# Gamepad_Sensors.net
KiCad netlist of a schematic drawn in Altium Designer
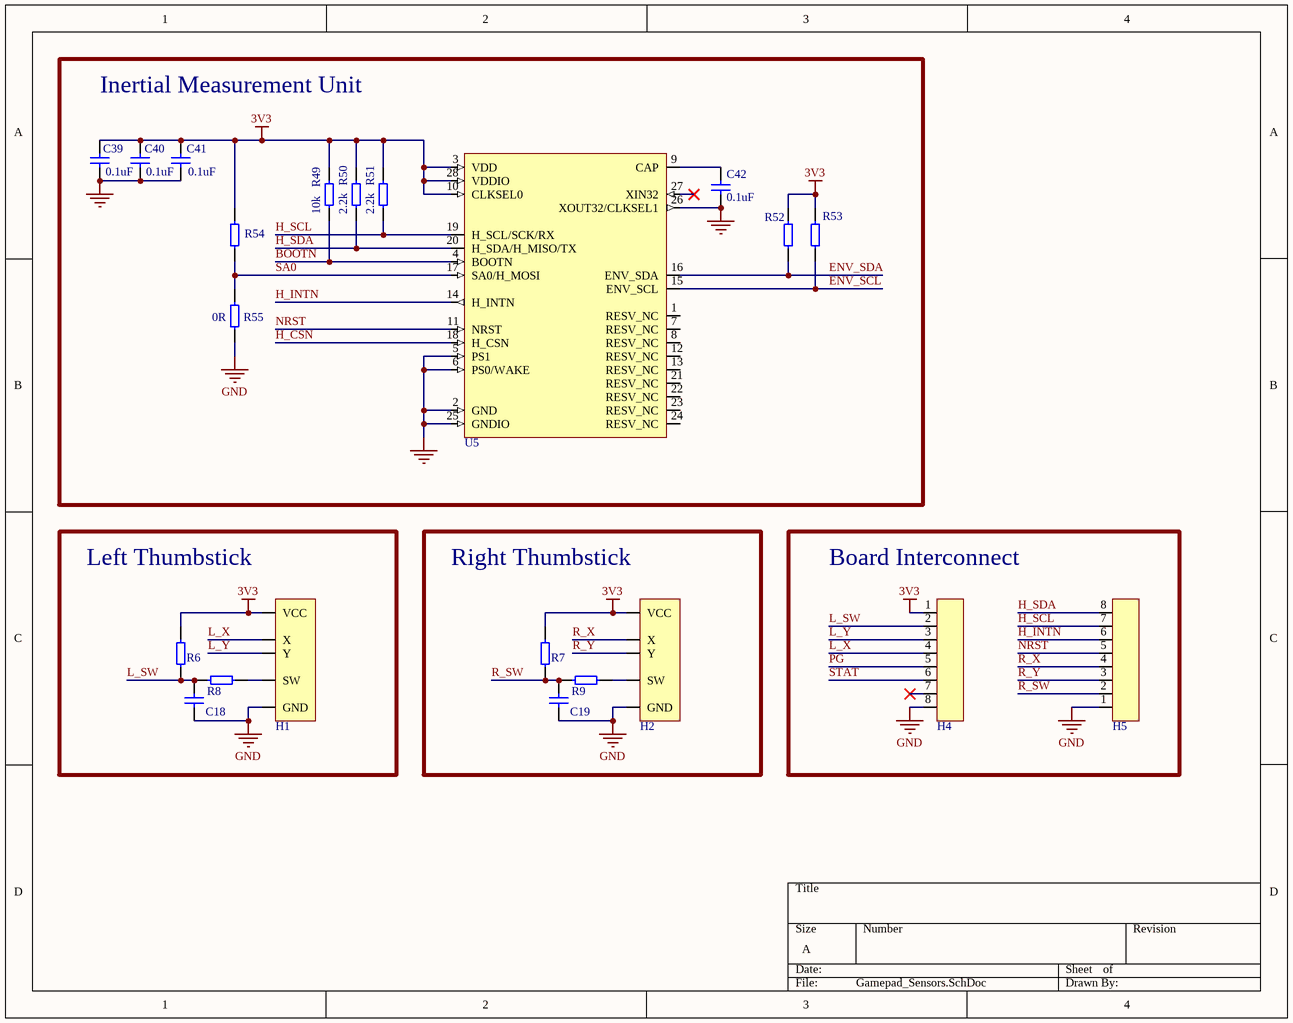
[diagram p0: Gamepad_Sensors.SchDoc]

(export (version "E")
  (design (tool "Eeschema 10.0.6"))
  (components
    (comp (ref "C18")
      (value "Capacitor")
      (footprint "0603 Capacitor")
      (libsource (lib "MoldsvorLibrary") (part "Capacitor"))
    )
    (comp (ref "C19")
      (value "Capacitor")
      (footprint "0603 Capacitor")
      (libsource (lib "MoldsvorLibrary") (part "Capacitor"))
    )
    (comp (ref "C39")
      (value "0.1uF")
      (footprint "0603 Capacitor")
      (libsource (lib "MoldsvorPassives") (part "Capacitor"))
    )
    (comp (ref "C40")
      (value "0.1uF")
      (footprint "0603 Capacitor")
      (libsource (lib "MoldsvorPassives") (part "Capacitor"))
    )
    (comp (ref "C41")
      (value "0.1uF")
      (footprint "0603 Capacitor")
      (libsource (lib "MoldsvorPassives") (part "Capacitor"))
    )
    (comp (ref "C42")
      (value "0.1uF")
      (footprint "0603 Capacitor")
      (libsource (lib "MoldsvorPassives") (part "Capacitor"))
    )
    (comp (ref "H1")
      (value "Left Thumbstick")
      (footprint "Thumbstick 2")
      (libsource (lib "Gamepad_Schematic_Library") (part "Thumbstick"))
    )
    (comp (ref "H2")
      (value "Right Thumbstick")
      (footprint "Thumbstick 2")
      (libsource (lib "Gamepad_Schematic_Library") (part "Thumbstick"))
    )
    (comp (ref "H4")
      (value "8x1 Header")
      (footprint "SMD Header Female")
      (libsource (lib "Gamepad_Schematic_Library") (part "8x1 Header"))
    )
    (comp (ref "H5")
      (value "8x1 Header")
      (footprint "SMD Header Female")
      (libsource (lib "") (part "8x1 Header_1"))
    )
    (comp (ref "R6")
      (value "Resistor")
      (footprint "0603 Resistor")
      (libsource (lib "MoldsvorLibrary") (part "Resistor"))
    )
    (comp (ref "R7")
      (value "Resistor")
      (footprint "0603 Resistor")
      (libsource (lib "MoldsvorLibrary") (part "Resistor"))
    )
    (comp (ref "R8")
      (value "Resistor")
      (footprint "0603 Resistor")
      (libsource (lib "MoldsvorLibrary") (part "Resistor"))
    )
    (comp (ref "R9")
      (value "Resistor")
      (footprint "0603 Resistor")
      (libsource (lib "MoldsvorLibrary") (part "Resistor"))
    )
    (comp (ref "R49")
      (value "10k")
      (footprint "0603 Resistor")
      (libsource (lib "MoldsvorLibrary") (part "Resistor"))
    )
    (comp (ref "R50")
      (value "2.2k")
      (footprint "0603 Resistor")
      (libsource (lib "MoldsvorPassives") (part "Resistor"))
    )
    (comp (ref "R51")
      (value "2.2k")
      (footprint "0603 Resistor")
      (libsource (lib "MoldsvorPassives") (part "Resistor"))
    )
    (comp (ref "R52")
      (value "Resistor")
      (footprint "0603 Resistor")
      (libsource (lib "MoldsvorPassives") (part "Resistor"))
    )
    (comp (ref "R53")
      (value "Resistor")
      (footprint "0603 Resistor")
      (libsource (lib "MoldsvorPassives") (part "Resistor"))
    )
    (comp (ref "R54")
      (value "Resistor")
      (footprint "0603 Resistor")
      (libsource (lib "MoldsvorLibrary") (part "Resistor"))
    )
    (comp (ref "R55")
      (value "0R")
      (footprint "0603 Resistor")
      (libsource (lib "MoldsvorLibrary") (part "Resistor"))
    )
    (comp (ref "U5")
      (value "BNO080")
      (footprint "BNO080")
      (description "IMU ACCEL/GYRO/MAG I2C 32BIT")
      (libsource (lib "Gamepad_Schematic_Library") (part "BNO080"))
    )
  )
  (nets
    (net (code "1") (name "/BOOTN") (class "Default")
      (node (ref "R49") (pin "1") (pintype "passive"))
      (node (ref "U5") (pin "4") (pinfunction "BOOTN_4") (pintype "input"))
    )
    (net (code "2") (name "/ENV_SCL") (class "Default")
      (node (ref "R53") (pin "1") (pintype "passive"))
      (node (ref "U5") (pin "15") (pinfunction "ENV_SCL_15") (pintype "bidirectional"))
    )
    (net (code "3") (name "/ENV_SDA") (class "Default")
      (node (ref "R52") (pin "1") (pintype "passive"))
      (node (ref "U5") (pin "16") (pinfunction "ENV_SDA_16") (pintype "bidirectional"))
    )
    (net (code "4") (name "/H_CSN") (class "Default")
      (node (ref "U5") (pin "18") (pinfunction "H_CSN_18") (pintype "input"))
    )
    (net (code "5") (name "/H_INTN") (class "Default")
      (node (ref "H5") (pin "6") (pinfunction "6_6") (pintype "passive"))
      (node (ref "U5") (pin "14") (pinfunction "H_INTN_14") (pintype "output"))
    )
    (net (code "6") (name "/H_SCL") (class "Default")
      (node (ref "H5") (pin "7") (pinfunction "7_7") (pintype "passive"))
      (node (ref "R51") (pin "1") (pintype "passive"))
      (node (ref "U5") (pin "19") (pinfunction "H_SCL/SCK/RX_19") (pintype "bidirectional"))
    )
    (net (code "7") (name "/H_SDA") (class "Default")
      (node (ref "H5") (pin "8") (pinfunction "8_8") (pintype "passive"))
      (node (ref "R50") (pin "1") (pintype "passive"))
      (node (ref "U5") (pin "20") (pinfunction "H_SDA/H_MISO/TX_20") (pintype "bidirectional"))
    )
    (net (code "8") (name "/L_SW") (class "Default")
      (node (ref "C18") (pin "2") (pinfunction "2_2") (pintype "passive"))
      (node (ref "H4") (pin "2") (pinfunction "2_2") (pintype "passive"))
      (node (ref "R6") (pin "1") (pintype "passive"))
      (node (ref "R8") (pin "1") (pintype "passive"))
    )
    (net (code "9") (name "/L_X") (class "Default")
      (node (ref "H1") (pin "2") (pinfunction "X_2") (pintype "passive"))
      (node (ref "H4") (pin "4") (pinfunction "4_4") (pintype "passive"))
    )
    (net (code "10") (name "/L_Y") (class "Default")
      (node (ref "H1") (pin "3") (pinfunction "Y_3") (pintype "passive"))
      (node (ref "H4") (pin "3") (pinfunction "3_3") (pintype "passive"))
    )
    (net (code "11") (name "/NRST") (class "Default")
      (node (ref "H5") (pin "5") (pinfunction "5_5") (pintype "passive"))
      (node (ref "U5") (pin "11") (pinfunction "NRST_11") (pintype "input"))
    )
    (net (code "12") (name "/PG") (class "Default")
      (node (ref "H4") (pin "5") (pinfunction "5_5") (pintype "passive"))
    )
    (net (code "13") (name "/R_SW") (class "Default")
      (node (ref "C19") (pin "2") (pinfunction "2_2") (pintype "passive"))
      (node (ref "H5") (pin "2") (pinfunction "2_2") (pintype "passive"))
      (node (ref "R7") (pin "1") (pintype "passive"))
      (node (ref "R9") (pin "1") (pintype "passive"))
    )
    (net (code "14") (name "/R_X") (class "Default")
      (node (ref "H2") (pin "2") (pinfunction "X_2") (pintype "passive"))
      (node (ref "H5") (pin "4") (pinfunction "4_4") (pintype "passive"))
    )
    (net (code "15") (name "/R_Y") (class "Default")
      (node (ref "H2") (pin "3") (pinfunction "Y_3") (pintype "passive"))
      (node (ref "H5") (pin "3") (pinfunction "3_3") (pintype "passive"))
    )
    (net (code "16") (name "/SA0") (class "Default")
      (node (ref "R54") (pin "1") (pintype "passive"))
      (node (ref "R55") (pin "2") (pintype "passive"))
      (node (ref "U5") (pin "17") (pinfunction "SA0/H_MOSI_17") (pintype "input"))
    )
    (net (code "17") (name "/STAT") (class "Default")
      (node (ref "H4") (pin "6") (pinfunction "6_6") (pintype "passive"))
    )
    (net (code "18") (name "3V3") (class "Default")
      (node (ref "C39") (pin "2") (pinfunction "2_2") (pintype "passive"))
      (node (ref "C40") (pin "1") (pinfunction "1_1") (pintype "passive"))
      (node (ref "C41") (pin "2") (pinfunction "2_2") (pintype "passive"))
      (node (ref "H1") (pin "1") (pinfunction "VCC_1") (pintype "passive"))
      (node (ref "H2") (pin "1") (pinfunction "VCC_1") (pintype "passive"))
      (node (ref "H4") (pin "1") (pinfunction "1_1") (pintype "passive"))
      (node (ref "R49") (pin "2") (pintype "passive"))
      (node (ref "R50") (pin "2") (pintype "passive"))
      (node (ref "R51") (pin "2") (pintype "passive"))
      (node (ref "R52") (pin "2") (pintype "passive"))
      (node (ref "R53") (pin "2") (pintype "passive"))
      (node (ref "R54") (pin "2") (pintype "passive"))
      (node (ref "R6") (pin "2") (pintype "passive"))
      (node (ref "R7") (pin "2") (pintype "passive"))
      (node (ref "U5") (pin "10") (pinfunction "CLKSEL0_10") (pintype "input"))
      (node (ref "U5") (pin "28") (pinfunction "VDDIO_28") (pintype "input"))
      (node (ref "U5") (pin "3") (pinfunction "VDD_3") (pintype "input"))
    )
    (net (code "19") (name "GND") (class "Default")
      (node (ref "C18") (pin "1") (pinfunction "1_1") (pintype "passive"))
      (node (ref "C19") (pin "1") (pinfunction "1_1") (pintype "passive"))
      (node (ref "C39") (pin "1") (pinfunction "1_1") (pintype "passive"))
      (node (ref "C40") (pin "2") (pinfunction "2_2") (pintype "passive"))
      (node (ref "C41") (pin "1") (pinfunction "1_1") (pintype "passive"))
      (node (ref "C42") (pin "1") (pinfunction "1_1") (pintype "passive"))
      (node (ref "H1") (pin "5") (pinfunction "GND_5") (pintype "passive"))
      (node (ref "H2") (pin "5") (pinfunction "GND_5") (pintype "passive"))
      (node (ref "H4") (pin "8") (pinfunction "8_8") (pintype "passive"))
      (node (ref "H5") (pin "1") (pinfunction "1_1") (pintype "passive"))
      (node (ref "R55") (pin "1") (pintype "passive"))
      (node (ref "U5") (pin "2") (pinfunction "GND_2") (pintype "input"))
      (node (ref "U5") (pin "25") (pinfunction "GNDIO_25") (pintype "input"))
      (node (ref "U5") (pin "26") (pinfunction "XOUT32/CLKSEL1_26") (pintype "output"))
      (node (ref "U5") (pin "5") (pinfunction "PS1_5") (pintype "input"))
      (node (ref "U5") (pin "6") (pinfunction "PS0/WAKE_6") (pintype "input"))
    )
    (net (code "20") (name "Net-(H1-SW)") (class "Default")
      (node (ref "H1") (pin "4") (pinfunction "SW_4") (pintype "passive"))
      (node (ref "R8") (pin "2") (pintype "passive"))
    )
    (net (code "21") (name "Net-(H2-SW)") (class "Default")
      (node (ref "H2") (pin "4") (pinfunction "SW_4") (pintype "passive"))
      (node (ref "R9") (pin "2") (pintype "passive"))
    )
    (net (code "22") (name "Net-(U5-CAP)") (class "Default")
      (node (ref "C42") (pin "2") (pinfunction "2_2") (pintype "passive"))
      (node (ref "U5") (pin "9") (pinfunction "CAP_9") (pintype "passive"))
    )
    (net (code "23") (name "unconnected-(H4-Pad7)") (class "Default")
      (node (ref "H4") (pin "7") (pinfunction "7_7") (pintype "passive+no_connect"))
    )
    (net (code "24") (name "unconnected-(U5-RESV_NC-Pad1)") (class "Default")
      (node (ref "U5") (pin "1") (pinfunction "RESV_NC_1") (pintype "passive"))
    )
    (net (code "25") (name "unconnected-(U5-RESV_NC-Pad7)") (class "Default")
      (node (ref "U5") (pin "7") (pinfunction "RESV_NC_7") (pintype "passive"))
    )
    (net (code "26") (name "unconnected-(U5-RESV_NC-Pad8)") (class "Default")
      (node (ref "U5") (pin "8") (pinfunction "RESV_NC_8") (pintype "passive"))
    )
    (net (code "27") (name "unconnected-(U5-RESV_NC-Pad12)") (class "Default")
      (node (ref "U5") (pin "12") (pinfunction "RESV_NC_12") (pintype "passive"))
    )
    (net (code "28") (name "unconnected-(U5-RESV_NC-Pad13)") (class "Default")
      (node (ref "U5") (pin "13") (pinfunction "RESV_NC_13") (pintype "passive"))
    )
    (net (code "29") (name "unconnected-(U5-RESV_NC-Pad21)") (class "Default")
      (node (ref "U5") (pin "21") (pinfunction "RESV_NC_21") (pintype "passive"))
    )
    (net (code "30") (name "unconnected-(U5-RESV_NC-Pad22)") (class "Default")
      (node (ref "U5") (pin "22") (pinfunction "RESV_NC_22") (pintype "passive"))
    )
    (net (code "31") (name "unconnected-(U5-RESV_NC-Pad23)") (class "Default")
      (node (ref "U5") (pin "23") (pinfunction "RESV_NC_23") (pintype "passive"))
    )
    (net (code "32") (name "unconnected-(U5-RESV_NC-Pad24)") (class "Default")
      (node (ref "U5") (pin "24") (pinfunction "RESV_NC_24") (pintype "passive"))
    )
    (net (code "33") (name "unconnected-(U5-XIN32-Pad27)") (class "Default")
      (node (ref "U5") (pin "27") (pinfunction "XIN32_27") (pintype "input+no_connect"))
    )
  )
)
